# Sheet1.net
KiCad netlist of a schematic drawn in Altium Designer
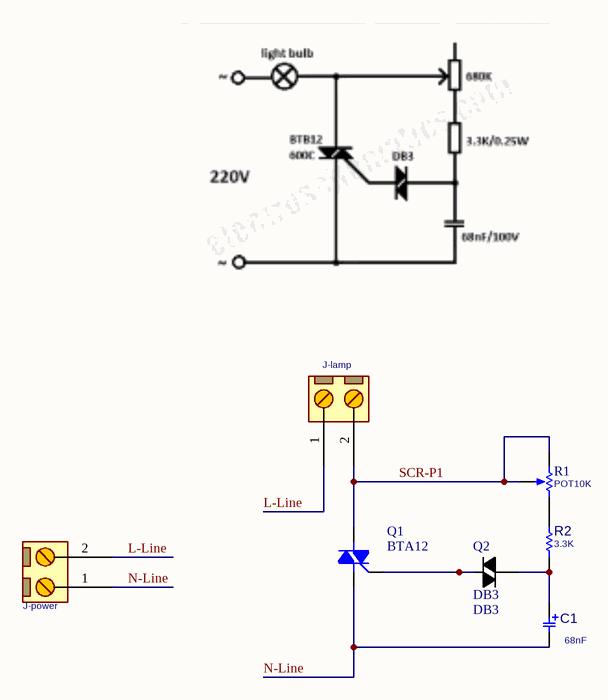
[diagram p0: Sheet1.SchDoc]

(export (version "E")
  (design (tool "Eeschema 10.0.6"))
  (components
    (comp (ref "C1")
      (value "68nF")
      (footprint "C_FLM_7X5H11")
      (description "CAP, THD, FILM,")
      (fields (field (name "MANF_P#") "MANF_PART#") (field (name "MANF") "MANF"))
      (libsource (lib "passive_thd") (part "CAP_THD_FLM"))
    )
    (comp (ref "J-lamp")
      (value "CONN_TB2")
      (footprint "MSTB_2")
      (description "CONN, PHOENIX MSTB, 5-G, 5.08mm pitch")
      (libsource (lib "conn_terminalB") (part "CONN_MSTB_2"))
    )
    (comp (ref "J-power")
      (value "CONN_TB2")
      (footprint "MSTB_2")
      (description "CONN, PHOENIX MSTB, 5-G, 5.08mm pitch")
      (libsource (lib "") (part "CONN_MSTB_2_1"))
    )
    (comp (ref "Q1")
      (value "BTA12")
      (footprint "TO220_3")
      (description "Triac, 600V, 12A, TO-220")
      (fields (field (name "MANF_P#") "BTA12-600BW, BTA12-600CW, BTA12-600TW") (field (name "MANF") "ST"))
      (libsource (lib "triac_diac") (part "TRIAC_BTA12-600_TO220"))
    )
    (comp (ref "Q2")
      (value "DB3")
      (footprint "D_AX03_DO35")
      (description "Diac, 32VBO, DO-35")
      (fields (field (name "MANF") "ST") (field (name "ALTIUM_VALUE") "DB3"))
      (libsource (lib "triac_diac") (part "DIAC_DB3_DO35"))
    )
    (comp (ref "R1")
      (value "POT10K")
      (footprint "VOL_R")
      (description "RESISTOR, THD, Potentiometer Volume")
      (libsource (lib "resistor_pot_trimmer") (part "RES_THD_POT_VOL"))
    )
    (comp (ref "R2")
      (value "3.3K")
      (footprint "R025W_AX04")
      (description "RESISTOR, THD")
      (fields (field (name "MANF_P#") "RK73H1ETTP4701F") (field (name "MANF") "KOA SPEER"))
      (libsource (lib "passive_thd") (part "RES_THD"))
    )
  )
  (nets
    (net (code "1") (name "/L-Line") (class "Default")
      (node (ref "J-lamp") (pin "1") (pinfunction "1_1") (pintype "passive"))
      (node (ref "J-power") (pin "2") (pinfunction "2_2") (pintype "passive"))
    )
    (net (code "2") (name "/N-Line") (class "Default")
      (node (ref "C1") (pin "2") (pinfunction "2_2") (pintype "passive"))
      (node (ref "J-power") (pin "1") (pinfunction "1_1") (pintype "passive"))
      (node (ref "Q1") (pin "1") (pinfunction "T1_1") (pintype "passive"))
    )
    (net (code "3") (name "/SCR-P1") (class "Default")
      (node (ref "J-lamp") (pin "2") (pinfunction "2_2") (pintype "passive"))
      (node (ref "Q1") (pin "2") (pinfunction "T2_2") (pintype "passive"))
      (node (ref "R1") (pin "1") (pinfunction "TOP_1") (pintype "passive"))
      (node (ref "R1") (pin "2") (pinfunction "TAP_2") (pintype "passive"))
    )
    (net (code "4") (name "Net-(Q1-G)") (class "Default")
      (node (ref "Q1") (pin "3") (pinfunction "G_3") (pintype "passive"))
      (node (ref "Q2") (pin "1") (pinfunction "A1_1") (pintype "passive"))
    )
    (net (code "5") (name "Net-(Q2-A2)") (class "Default")
      (node (ref "C1") (pin "1") (pinfunction "1_1") (pintype "passive"))
      (node (ref "Q2") (pin "2") (pinfunction "A2_2") (pintype "passive"))
      (node (ref "R2") (pin "2") (pinfunction "2_2") (pintype "passive"))
    )
    (net (code "6") (name "Net-(R1-BOT)") (class "Default")
      (node (ref "R1") (pin "3") (pinfunction "BOT_3") (pintype "passive"))
      (node (ref "R2") (pin "1") (pinfunction "1_1") (pintype "passive"))
    )
  )
)
